# ArbPwrBoost_P2.net
KiCad netlist of a schematic drawn in Altium Designer
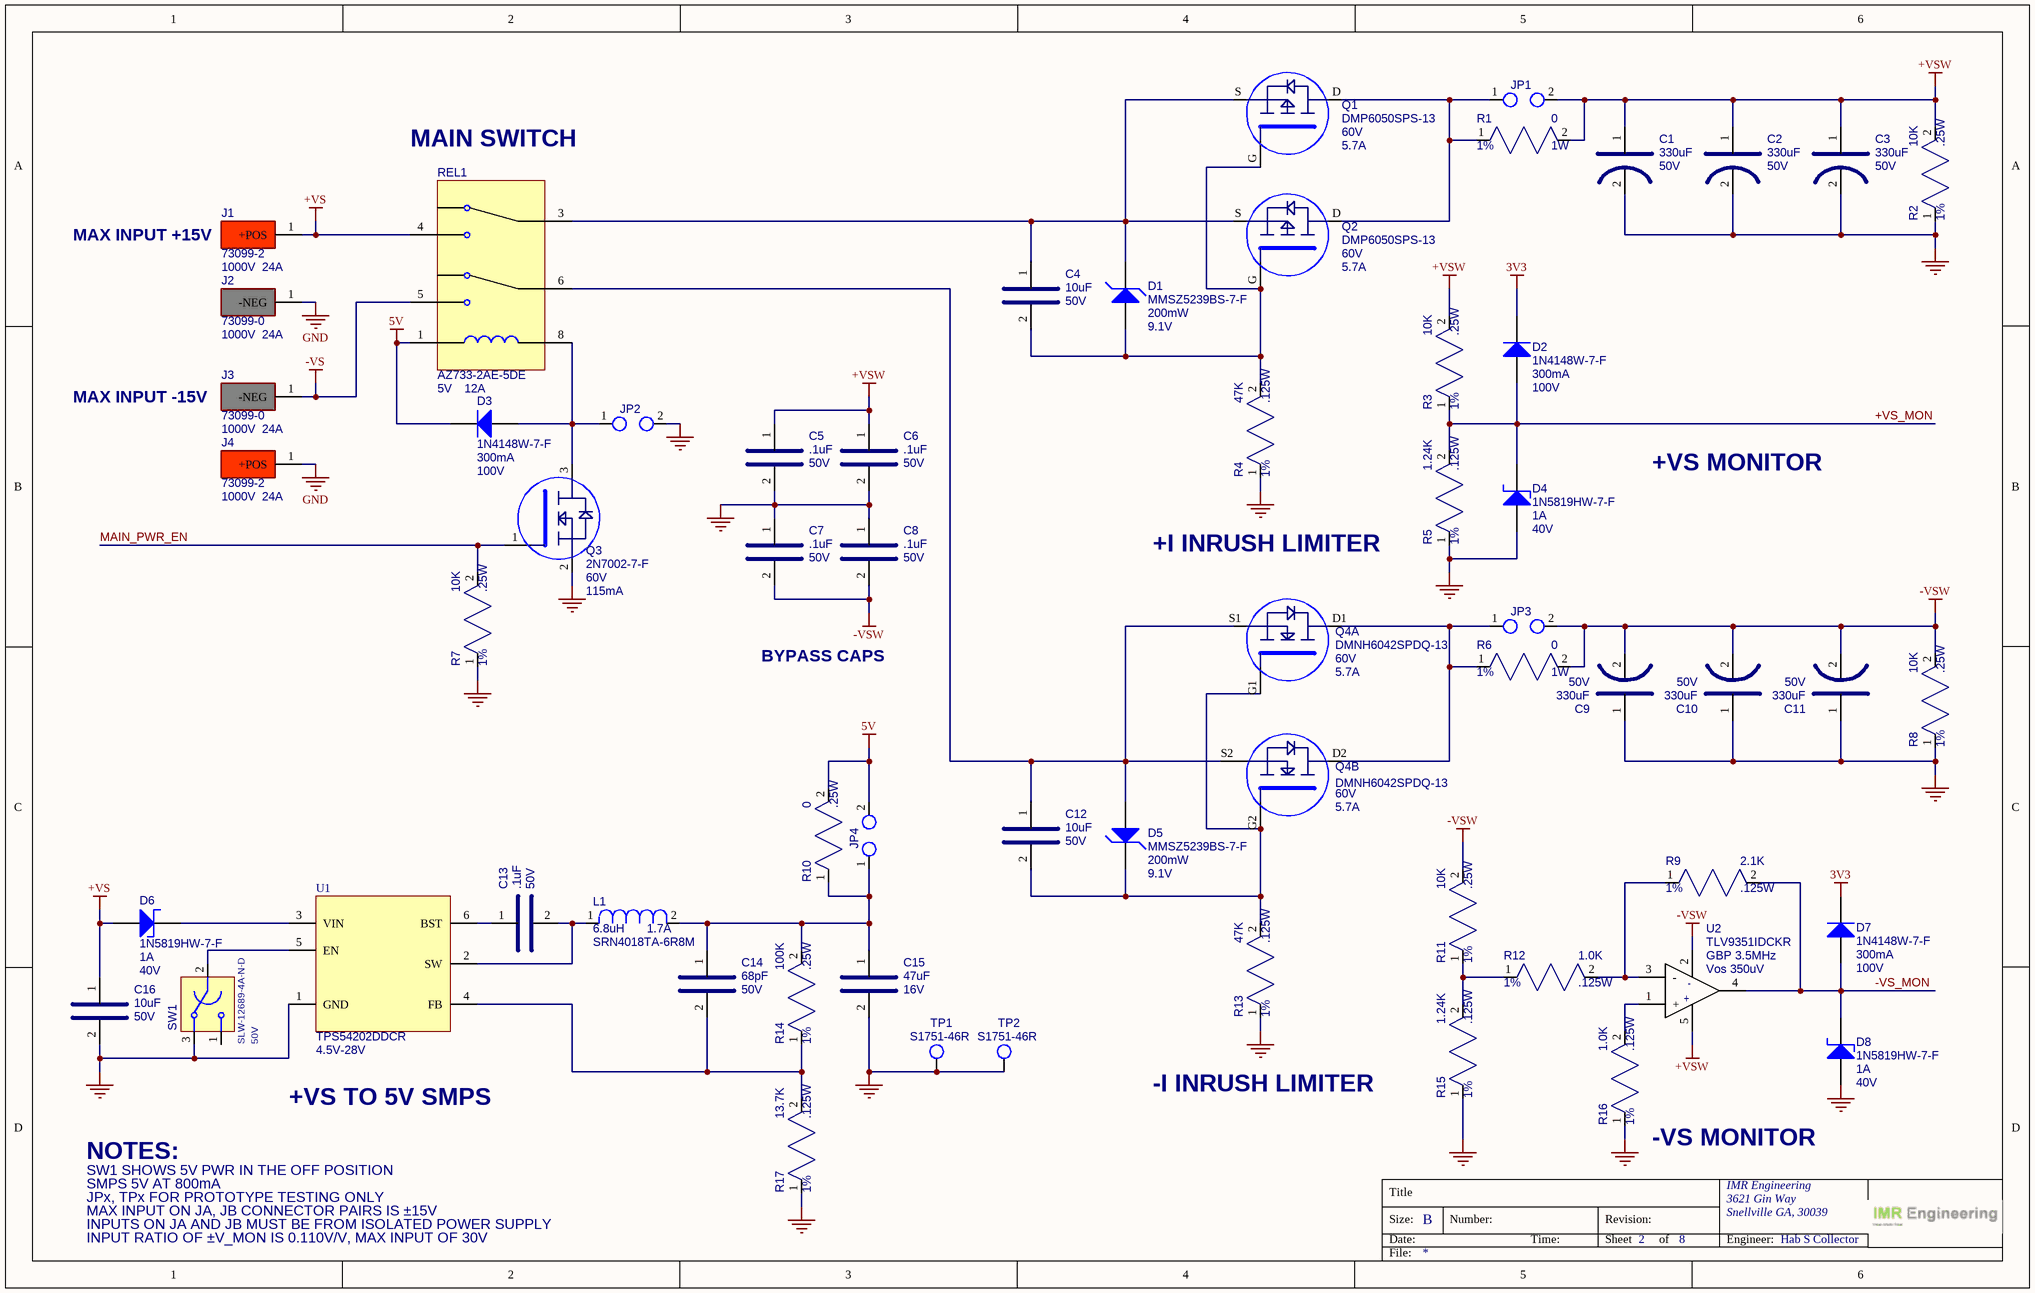
[diagram p0: ArbPwrBoost_P2.SchDoc]

(export (version "E")
  (design (tool "Eeschema 10.0.6"))
  (components
    (comp (ref "C1")
      (value "330uF")
      (footprint "PANASONIC_EEEFK0J332AQ")
      (description "CAP ALE 330UF 20% 50V SMD")
      (fields
        (field (name "MFG") "EEV-FK1H331Q")
        (field (name "VOLTAGE") "50V")
        (field (name "Comment") "Panasonic Electronic")
      )
      (libsource (lib "IMR_LIB_SCH_R2") (part "CAP_330UF_50V_ALE"))
    )
    (comp (ref "C2")
      (value "330uF")
      (footprint "PANASONIC_EEEFK0J332AQ")
      (description "CAP ALE 330UF 20% 50V SMD")
      (fields
        (field (name "MFG") "EEV-FK1H331Q")
        (field (name "VOLTAGE") "50V")
        (field (name "Comment") "Panasonic Electronic")
      )
      (libsource (lib "IMR_LIB_SCH_R2") (part "CAP_330UF_50V_ALE"))
    )
    (comp (ref "C3")
      (value "330uF")
      (footprint "PANASONIC_EEEFK0J332AQ")
      (description "CAP ALE 330UF 20% 50V SMD")
      (fields
        (field (name "MFG") "EEV-FK1H331Q")
        (field (name "VOLTAGE") "50V")
        (field (name "Comment") "Panasonic Electronic")
      )
      (libsource (lib "IMR_LIB_SCH_R2") (part "CAP_330UF_50V_ALE"))
    )
    (comp (ref "C4")
      (value "10uF")
      (footprint "CAP_0805")
      (description "CAP CER 10UF 50V X5R 0805")
      (fields
        (field (name "MFG") "Murata Electronics")
        (field (name "VOLTAGE") "50V")
        (field (name "Comment") "GRM21BR61H106KE43L")
      )
      (libsource (lib "IMR_LIB_SCH_R2") (part "CAP_SMD_10UF_50V_0805"))
    )
    (comp (ref "C5")
      (value ".1uF")
      (footprint "CAP_0805")
      (description "CAP CER 0.1UF 50V X7R 0805")
      (fields
        (field (name "MFG") "KYOCERA AVX")
        (field (name "VOLTAGE") "50V")
        (field (name "Comment") "KGM21NR71H104KT")
      )
      (libsource (lib "IMR_LIB_SCH_R2") (part "CAP_SMD_0.1UF_50V_0805"))
    )
    (comp (ref "C6")
      (value ".1uF")
      (footprint "CAP_0805")
      (description "CAP CER 0.1UF 50V X7R 0805")
      (fields
        (field (name "MFG") "KYOCERA AVX")
        (field (name "VOLTAGE") "50V")
        (field (name "Comment") "KGM21NR71H104KT")
      )
      (libsource (lib "IMR_LIB_SCH_R2") (part "CAP_SMD_0.1UF_50V_0805"))
    )
    (comp (ref "C7")
      (value ".1uF")
      (footprint "CAP_0805")
      (description "CAP CER 0.1UF 50V X7R 0805")
      (fields
        (field (name "MFG") "KYOCERA AVX")
        (field (name "VOLTAGE") "50V")
        (field (name "Comment") "KGM21NR71H104KT")
      )
      (libsource (lib "IMR_LIB_SCH_R2") (part "CAP_SMD_0.1UF_50V_0805"))
    )
    (comp (ref "C8")
      (value ".1uF")
      (footprint "CAP_0805")
      (description "CAP CER 0.1UF 50V X7R 0805")
      (fields
        (field (name "MFG") "KYOCERA AVX")
        (field (name "VOLTAGE") "50V")
        (field (name "Comment") "KGM21NR71H104KT")
      )
      (libsource (lib "IMR_LIB_SCH_R2") (part "CAP_SMD_0.1UF_50V_0805"))
    )
    (comp (ref "C9")
      (value "330uF")
      (footprint "PANASONIC_EEEFK0J332AQ")
      (description "CAP ALE 330UF 20% 50V SMD")
      (fields
        (field (name "MFG") "EEV-FK1H331Q")
        (field (name "VOLTAGE") "50V")
        (field (name "Comment") "Panasonic Electronic")
      )
      (libsource (lib "IMR_LIB_SCH_R2") (part "CAP_330UF_50V_ALE"))
    )
    (comp (ref "C10")
      (value "330uF")
      (footprint "PANASONIC_EEEFK0J332AQ")
      (description "CAP ALE 330UF 20% 50V SMD")
      (fields
        (field (name "MFG") "EEV-FK1H331Q")
        (field (name "VOLTAGE") "50V")
        (field (name "Comment") "Panasonic Electronic")
      )
      (libsource (lib "IMR_LIB_SCH_R2") (part "CAP_330UF_50V_ALE"))
    )
    (comp (ref "C11")
      (value "330uF")
      (footprint "PANASONIC_EEEFK0J332AQ")
      (description "CAP ALE 330UF 20% 50V SMD")
      (fields
        (field (name "MFG") "EEV-FK1H331Q")
        (field (name "VOLTAGE") "50V")
        (field (name "Comment") "Panasonic Electronic")
      )
      (libsource (lib "IMR_LIB_SCH_R2") (part "CAP_330UF_50V_ALE"))
    )
    (comp (ref "C12")
      (value "10uF")
      (footprint "CAP_0805")
      (description "CAP CER 10UF 50V X5R 0805")
      (fields
        (field (name "MFG") "Murata Electronics")
        (field (name "VOLTAGE") "50V")
        (field (name "Comment") "GRM21BR61H106KE43L")
      )
      (libsource (lib "IMR_LIB_SCH_R2") (part "CAP_SMD_10UF_50V_0805"))
    )
    (comp (ref "C13")
      (value ".1uF")
      (footprint "CAP_0805")
      (description "CAP CER 0.1UF 50V X7R 0805")
      (fields
        (field (name "MFG") "KYOCERA AVX")
        (field (name "VOLTAGE") "50V")
        (field (name "Comment") "KGM21NR71H104KT")
      )
      (libsource (lib "IMR_LIB_SCH_R2") (part "CAP_SMD_0.1UF_50V_0805"))
    )
    (comp (ref "C14")
      (value "68pF")
      (footprint "CAP_0805")
      (description "CAP CER 68PF 50V X7R 0805")
      (fields
        (field (name "MFG") "KEMET")
        (field (name "VOLTAGE") "50V")
        (field (name "Comment") "C0805C680K5RACAUTO")
      )
      (libsource (lib "IMR_LIB_SCH_R2") (part "CAP_SMD_68PF_50V_0805"))
    )
    (comp (ref "C15")
      (value "47uF")
      (footprint "CAP_1210")
      (description "CAP CER 47UF 50V X5R 1210")
      (fields
        (field (name "MFG") "Murata Electronics")
        (field (name "VOLTAGE") "16V")
        (field (name "Comment") "GRM32ER60J476ME20L")
      )
      (libsource (lib "IMR_LIB_SCH_R2") (part "CAP_SMD_47UF_16V_1210"))
    )
    (comp (ref "C16")
      (value "10uF")
      (footprint "CAP_0805")
      (description "CAP CER 10UF 50V X5R 0805")
      (fields
        (field (name "MFG") "Murata Electronics")
        (field (name "VOLTAGE") "50V")
        (field (name "Comment") "GRM21BR61H106KE43L")
      )
      (libsource (lib "IMR_LIB_SCH_R2") (part "CAP_SMD_10UF_50V_0805"))
    )
    (comp (ref "D1")
      (value "9.1V")
      (footprint "SOD323")
      (description "DIODE ZENER 9.1V 200MW SOD323")
      (fields
        (field (name "MFG") "Diodes Inc")
        (field (name "MFG_PN") "MMSZ5239BS-7-F")
        (field (name "POWER") "200mW")
        (field (name "Comment") "MMSZ5239BS-7-F")
      )
      (libsource (lib "IMR_LIB_SCH_R2") (part "DIODE_ZENER_MMSZ5239BS-7-F"))
    )
    (comp (ref "D2")
      (value "100V")
      (footprint "SOD123")
      (description "RELAY REED SPDT 250MA 5V")
      (fields
        (field (name "MFG") "Diodes Inc")
        (field (name "MFG_PN") "1N4148W-7-F")
        (field (name "CURRENT") "300mA")
        (field (name "Comment") "1N4148W-7-F")
      )
      (libsource (lib "IMR_LIB_SCH_R2") (part "DIODE_1N4148W-7-F"))
    )
    (comp (ref "D3")
      (value "100V")
      (footprint "SOD123")
      (description "RELAY REED SPDT 250MA 5V")
      (fields
        (field (name "MFG") "Diodes Inc")
        (field (name "MFG_PN") "1N4148W-7-F")
        (field (name "CURRENT") "300mA")
        (field (name "Comment") "1N4148W-7-F")
      )
      (libsource (lib "IMR_LIB_SCH_R2") (part "DIODE_1N4148W-7-F"))
    )
    (comp (ref "D4")
      (value "40V")
      (footprint "SOD123")
      (description "DIODE SCHOTTKY 40V 1A SOD123")
      (fields
        (field (name "MFG") "Diodes Inc")
        (field (name "MFG_PN") "1N5819HW-7-F")
        (field (name "CURRENT") "1A")
        (field (name "Comment") "1N5819HW-7-F")
      )
      (libsource (lib "IMR_LIB_SCH_R2") (part "DIODE_SCHOTTKY_1N5819HW-7-F"))
    )
    (comp (ref "D5")
      (value "9.1V")
      (footprint "SOD323")
      (description "DIODE ZENER 9.1V 200MW SOD323")
      (fields
        (field (name "MFG") "Diodes Inc")
        (field (name "MFG_PN") "MMSZ5239BS-7-F")
        (field (name "POWER") "200mW")
        (field (name "Comment") "MMSZ5239BS-7-F")
      )
      (libsource (lib "IMR_LIB_SCH_R2") (part "DIODE_ZENER_MMSZ5239BS-7-F"))
    )
    (comp (ref "D6")
      (value "40V")
      (footprint "SOD123")
      (description "DIODE SCHOTTKY 40V 1A SOD123")
      (fields
        (field (name "MFG") "Diodes Inc")
        (field (name "MFG_PN") "1N5819HW-7-F")
        (field (name "CURRENT") "1A")
        (field (name "Comment") "1N5819HW-7-F")
      )
      (libsource (lib "IMR_LIB_SCH_R2") (part "DIODE_SCHOTTKY_1N5819HW-7-F"))
    )
    (comp (ref "D7")
      (value "100V")
      (footprint "SOD123")
      (description "RELAY REED SPDT 250MA 5V")
      (fields
        (field (name "MFG") "Diodes Inc")
        (field (name "MFG_PN") "1N4148W-7-F")
        (field (name "CURRENT") "300mA")
        (field (name "Comment") "1N4148W-7-F")
      )
      (libsource (lib "IMR_LIB_SCH_R2") (part "DIODE_1N4148W-7-F"))
    )
    (comp (ref "D8")
      (value "40V")
      (footprint "SOD123")
      (description "DIODE SCHOTTKY 40V 1A SOD123")
      (fields
        (field (name "MFG") "Diodes Inc")
        (field (name "MFG_PN") "1N5819HW-7-F")
        (field (name "CURRENT") "1A")
        (field (name "Comment") "1N5819HW-7-F")
      )
      (libsource (lib "IMR_LIB_SCH_R2") (part "DIODE_SCHOTTKY_1N5819HW-7-F"))
    )
    (comp (ref "J1")
      (value "1000V")
      (footprint "Pomona_73099-2")
      (description "CONN 4mm Banana Socket Right Angle PCB RED")
      (fields
        (field (name "MFG") "Pomona")
        (field (name "MFG_PN") "73099-2")
        (field (name "CURRENT") "24A")
        (field (name "Comment") "73099-2")
      )
      (libsource (lib "IMR_LIB_SCH_R2") (part "CONN_PANOMA_73099-2"))
    )
    (comp (ref "J2")
      (value "1000V")
      (footprint "Pomona_73099-0")
      (description "CONN 4mm Banana Socket Right Angle PCB BLK")
      (fields
        (field (name "MFG") "Pomona")
        (field (name "MFG_PN") "73099-0")
        (field (name "CURRENT") "24A")
        (field (name "Comment") "73099-0")
      )
      (libsource (lib "IMR_LIB_SCH_R2") (part "CONN_PANOMA_73099-0"))
    )
    (comp (ref "J3")
      (value "1000V")
      (footprint "Pomona_73099-0")
      (description "CONN 4mm Banana Socket Right Angle PCB BLK")
      (fields
        (field (name "MFG") "Pomona")
        (field (name "MFG_PN") "73099-0")
        (field (name "CURRENT") "24A")
        (field (name "Comment") "73099-0")
      )
      (libsource (lib "IMR_LIB_SCH_R2") (part "CONN_PANOMA_73099-0"))
    )
    (comp (ref "J4")
      (value "1000V")
      (footprint "Pomona_73099-2")
      (description "CONN 4mm Banana Socket Right Angle PCB RED")
      (fields
        (field (name "MFG") "Pomona")
        (field (name "MFG_PN") "73099-2")
        (field (name "CURRENT") "24A")
        (field (name "Comment") "73099-2")
      )
      (libsource (lib "IMR_LIB_SCH_R2") (part "CONN_PANOMA_73099-2"))
    )
    (comp (ref "JP1")
      (value "PREC002SFAN-RC")
      (footprint "HDR_1X2_100MILL")
      (description "CONN HEADER VERT 2POS 2.54MM")
      (fields (field (name "MFG") "Sullins Connector Solutions"))
      (libsource (lib "IMR_LIB_SCH_R2") (part "CONN_JUMPER_2P_100MIL_VERT"))
    )
    (comp (ref "JP2")
      (value "PREC002SFAN-RC")
      (footprint "HDR_1X2_100MILL")
      (description "CONN HEADER VERT 2POS 2.54MM")
      (fields (field (name "MFG") "Sullins Connector Solutions"))
      (libsource (lib "IMR_LIB_SCH_R2") (part "CONN_JUMPER_2P_100MIL_VERT"))
    )
    (comp (ref "JP3")
      (value "PREC002SFAN-RC")
      (footprint "HDR_1X2_100MILL")
      (description "CONN HEADER VERT 2POS 2.54MM")
      (fields (field (name "MFG") "Sullins Connector Solutions"))
      (libsource (lib "IMR_LIB_SCH_R2") (part "CONN_JUMPER_2P_100MIL_VERT"))
    )
    (comp (ref "JP4")
      (value "PREC002SFAN-RC")
      (footprint "HDR_1X2_100MILL")
      (description "CONN HEADER VERT 2POS 2.54MM")
      (fields (field (name "MFG") "Sullins Connector Solutions"))
      (libsource (lib "IMR_LIB_SCH_R2") (part "CONN_JUMPER_2P_100MIL_VERT"))
    )
    (comp (ref "L1")
      (value "6.8uH")
      (footprint "SRN4018TA")
      (description "FIXED IND 6.8UH 1.7A 98 MOHM SMD")
      (fields
        (field (name "MFG") "Bourns Inc.")
        (field (name "TOLERANCE") "20%")
        (field (name "MFG_PN") "SRN4018TA-6R8M")
        (field (name "CURRENT") "1.7A")
      )
      (libsource (lib "IMR_LIB_SCH_R2") (part "INDUCTOR_SRN4018TA-6R8M"))
    )
    (comp (ref "Q1")
      (value "60V")
      (footprint "DMP3007SPS13")
      (description "MOSFET P-CH 60V 5.7A PWRDI5060-8")
      (fields
        (field (name "MFG") "Diodes Inc")
        (field (name "MFG_PN") "DMP6050SPS-13")
        (field (name "CURRENT") "5.7A")
        (field (name "Comment") "DMP6050SPS-13")
      )
      (libsource (lib "IMR_LIB_SCH_R2") (part "MOSFET_PCH_DMP6050SPS-13"))
    )
    (comp (ref "Q2")
      (value "60V")
      (footprint "DMP3007SPS13")
      (description "MOSFET P-CH 60V 5.7A PWRDI5060-8")
      (fields
        (field (name "MFG") "Diodes Inc")
        (field (name "MFG_PN") "DMP6050SPS-13")
        (field (name "CURRENT") "5.7A")
        (field (name "Comment") "DMP6050SPS-13")
      )
      (libsource (lib "IMR_LIB_SCH_R2") (part "MOSFET_PCH_DMP6050SPS-13"))
    )
    (comp (ref "Q3")
      (value "60V")
      (footprint "SOT-23")
      (description "MOSFET N-CH 60V 115MA SOT23-3")
      (fields
        (field (name "MFG") "Diodes Inc")
        (field (name "MFG_PN") "2N7002-7-F")
        (field (name "CURRENT") "115mA")
        (field (name "Comment") "2N7002-7-F")
      )
      (libsource (lib "IMR_LIB_SCH_R2") (part "MOSFET_NCH_2N7002-7-F"))
    )
    (comp (ref "Q4")
      (value "60V")
      (footprint "TRANS_DMP2002UPS-13")
      (description "MOSFET NCH 60V 5.7A POWERDI")
      (fields
        (field (name "MFG") "Diodes Inc")
        (field (name "MFG_PN") "DMNH6042SPDQ-13")
        (field (name "CURRENT") "5.7A")
        (field (name "Comment") "DMNH6042SPDQ-13")
      )
      (libsource (lib "IMR_LIB_SCH_R2") (part "MOSFET_NCH_DMNH6042SPDQ-13"))
    )
    (comp (ref "R1")
      (value "0")
      (footprint "RES_2512")
      (description "RES SMD 0 OHM 1% 1W 2512")
      (fields
        (field (name "MFG") "Yageo")
        (field (name "TOLERANCE") "1%")
        (field (name "POWER") "1W")
        (field (name "Comment") "RC2512JK-070RL")
      )
      (libsource (lib "IMR_LIB_SCH_R2") (part "RES_SMD_0_2512_1W_1%"))
    )
    (comp (ref "R2")
      (value "10K")
      (footprint "RES_0805")
      (description "RES SMD 10K OHM 1% 1/4W 0805")
      (fields
        (field (name "MFG") "Yageo")
        (field (name "POWER") ".25W")
        (field (name "TOLERANCE") "1%")
        (field (name "Comment") "RC0805FR-7W10KL")
      )
      (libsource (lib "IMR_LIB_SCH_R2") (part "RES_SMD_10K_0805_1/4W_1%"))
    )
    (comp (ref "R3")
      (value "10K")
      (footprint "RES_0805")
      (description "RES SMD 10K OHM 1% 1/4W 0805")
      (fields
        (field (name "MFG") "Yageo")
        (field (name "POWER") ".25W")
        (field (name "TOLERANCE") "1%")
        (field (name "Comment") "RC0805FR-7W10KL")
      )
      (libsource (lib "IMR_LIB_SCH_R2") (part "RES_SMD_10K_0805_1/4W_1%"))
    )
    (comp (ref "R4")
      (value "47K")
      (footprint "RES_0805")
      (description "RES SMD 47K OHM 1% 1/8W 0805")
      (fields
        (field (name "MFG") "Yageo")
        (field (name "POWER") ".125W")
        (field (name "TOLERANCE") "1%")
        (field (name "Comment") "RC0805FR-1347KL")
      )
      (libsource (lib "IMR_LIB_SCH_R2") (part "RES_SMD_47K_0805_1/8W_1%"))
    )
    (comp (ref "R5")
      (value "1.24K")
      (footprint "RES_0805")
      (description "RES SMD 1.24K OHM 1% 1/8W 0805")
      (fields
        (field (name "MFG") "Yageo")
        (field (name "POWER") ".125W")
        (field (name "TOLERANCE") "1%")
        (field (name "Comment") "RC0805FR-071K24L")
      )
      (libsource (lib "IMR_LIB_SCH_R2") (part "RES_SMD_1.24K_0805_1/8W_1%"))
    )
    (comp (ref "R6")
      (value "0")
      (footprint "RES_2512")
      (description "RES SMD 0 OHM 1% 1W 2512")
      (fields
        (field (name "MFG") "Yageo")
        (field (name "TOLERANCE") "1%")
        (field (name "POWER") "1W")
        (field (name "Comment") "RC2512JK-070RL")
      )
      (libsource (lib "IMR_LIB_SCH_R2") (part "RES_SMD_0_2512_1W_1%"))
    )
    (comp (ref "R7")
      (value "10K")
      (footprint "RES_0805")
      (description "RES SMD 10K OHM 1% 1/4W 0805")
      (fields
        (field (name "MFG") "Yageo")
        (field (name "POWER") ".25W")
        (field (name "TOLERANCE") "1%")
        (field (name "Comment") "RC0805FR-7W10KL")
      )
      (libsource (lib "IMR_LIB_SCH_R2") (part "RES_SMD_10K_0805_1/4W_1%"))
    )
    (comp (ref "R8")
      (value "10K")
      (footprint "RES_0805")
      (description "RES SMD 10K OHM 1% 1/4W 0805")
      (fields
        (field (name "MFG") "Yageo")
        (field (name "POWER") ".25W")
        (field (name "TOLERANCE") "1%")
        (field (name "Comment") "RC0805FR-7W10KL")
      )
      (libsource (lib "IMR_LIB_SCH_R2") (part "RES_SMD_10K_0805_1/4W_1%"))
    )
    (comp (ref "R9")
      (value "2.1K")
      (footprint "RES_0805")
      (description "RES SMD 2.1K OHM 1% 1/8W 0805")
      (fields
        (field (name "MFG") "Yageo")
        (field (name "POWER") ".125W")
        (field (name "TOLERANCE") "1%")
        (field (name "Comment") "RC0805FR-072K1L")
      )
      (libsource (lib "IMR_LIB_SCH_R2") (part "RES_SMD_2.1K_0805_1/8W_1%"))
    )
    (comp (ref "R10")
      (value "0")
      (footprint "RES_0805")
      (description "RES SMD 0 OHM 1% 1/8W 0805")
      (fields (field (name "MFG") "Yageo") (field (name "TOLERANCE") "1%") (field (name "POWER") ".25W"))
      (libsource (lib "IMR_LIB_SCH_R2") (part "RES_SMD_0_0805_1/8W_1%"))
    )
    (comp (ref "R11")
      (value "10K")
      (footprint "RES_0805")
      (description "RES SMD 10K OHM 1% 1/4W 0805")
      (fields
        (field (name "MFG") "Yageo")
        (field (name "POWER") ".25W")
        (field (name "TOLERANCE") "1%")
        (field (name "Comment") "RC0805FR-7W10KL")
      )
      (libsource (lib "IMR_LIB_SCH_R2") (part "RES_SMD_10K_0805_1/4W_1%"))
    )
    (comp (ref "R12")
      (value "1.0K")
      (footprint "RES_0805")
      (description "RES SMD 1.0K OHM 1% 1/8W 0805")
      (fields
        (field (name "MFG") "Yageo")
        (field (name "POWER") ".125W")
        (field (name "TOLERANCE") "1%")
        (field (name "Comment") "RC0805FR-071KL")
      )
      (libsource (lib "IMR_LIB_SCH_R2") (part "RES_SMD_1.0K_0805_1/8W_1%"))
    )
    (comp (ref "R13")
      (value "47K")
      (footprint "RES_0805")
      (description "RES SMD 47K OHM 1% 1/8W 0805")
      (fields
        (field (name "MFG") "Yageo")
        (field (name "POWER") ".125W")
        (field (name "TOLERANCE") "1%")
        (field (name "Comment") "RC0805FR-1347KL")
      )
      (libsource (lib "IMR_LIB_SCH_R2") (part "RES_SMD_47K_0805_1/8W_1%"))
    )
    (comp (ref "R14")
      (value "100K")
      (footprint "RES_0805")
      (description "RES SMD 100K OHM 1% 1/4W 0805")
      (fields
        (field (name "MFG") "Yageo")
        (field (name "POWER") ".25W")
        (field (name "TOLERANCE") "1%")
        (field (name "Comment") "RC0805FR-07100KL")
      )
      (libsource (lib "IMR_LIB_SCH_R2") (part "RES_SMD_100K_0805_1/4W_1%"))
    )
    (comp (ref "R15")
      (value "1.24K")
      (footprint "RES_0805")
      (description "RES SMD 1.24K OHM 1% 1/8W 0805")
      (fields
        (field (name "MFG") "Yageo")
        (field (name "POWER") ".125W")
        (field (name "TOLERANCE") "1%")
        (field (name "Comment") "RC0805FR-071K24L")
      )
      (libsource (lib "IMR_LIB_SCH_R2") (part "RES_SMD_1.24K_0805_1/8W_1%"))
    )
    (comp (ref "R16")
      (value "1.0K")
      (footprint "RES_0805")
      (description "RES SMD 1.0K OHM 1% 1/8W 0805")
      (fields
        (field (name "MFG") "Yageo")
        (field (name "POWER") ".125W")
        (field (name "TOLERANCE") "1%")
        (field (name "Comment") "RC0805FR-071KL")
      )
      (libsource (lib "IMR_LIB_SCH_R2") (part "RES_SMD_1.0K_0805_1/8W_1%"))
    )
    (comp (ref "R17")
      (value "13.7K")
      (footprint "RES_0805")
      (description "RES SMD 13.7K OHM 1% 1/8W 0805")
      (fields
        (field (name "MFG") "Yageo")
        (field (name "POWER") ".125W")
        (field (name "TOLERANCE") "1%")
        (field (name "Comment") "RC0805FR-0713K7L")
      )
      (libsource (lib "IMR_LIB_SCH_R2") (part "RES_SMD_13.7K_0805_1/8W_1%"))
    )
    (comp (ref "REL1")
      (value "5V")
      (footprint "AZ733")
      (description "RELAY REED SPDT 250MA 5V")
      (fields
        (field (name "MFG") "American Zettler")
        (field (name "MFG_PN") "AZ733-2AE-5DE")
        (field (name "CURRENT") "12A")
        (field (name "Comment") "AZ733-2AE-5DE")
      )
      (libsource (lib "IMR_LIB_SCH_R2") (part "RELAY_AZ733-2AE-5DE"))
    )
    (comp (ref "SW1")
      (value "50V")
      (footprint "SLW126894AND")
      (description "SWITCH SLIDE SPDT 300MA 50V")
      (fields
        (field (name "MFG") "Same Sky")
        (field (name "MFG_PN") "SLW-12689-4A-N-D")
        (field (name "Comment") "SLW-12689-4A-N-D")
      )
      (libsource (lib "IMR_LIB_SCH_R2") (part "SWITCH_SLW-12689-4A-N-D"))
    )
    (comp (ref "TP1")
      (value "S1751-46R")
      (footprint "HARWIN_S1751")
      (description "PCB TEST POINT CONNECT")
      (fields (field (name "MFG") "Harwin Inc") (field (name "MFG_PN") "S1751-46R"))
      (libsource (lib "IMR_LIB_SCH_R2") (part "CONN_TEST_POINT_S1751-46R"))
    )
    (comp (ref "TP2")
      (value "S1751-46R")
      (footprint "HARWIN_S1751")
      (description "PCB TEST POINT CONNECT")
      (fields (field (name "MFG") "Harwin Inc") (field (name "MFG_PN") "S1751-46R"))
      (libsource (lib "IMR_LIB_SCH_R2") (part "CONN_TEST_POINT_S1751-46R"))
    )
    (comp (ref "U1")
      (value "4.5V-28V")
      (footprint "SOT-23-6")
      (description "IC REG BUCK ADJ 2A SOT23")
      (fields
        (field (name "MFG") "Texas Instruments")
        (field (name "MFG_PN") "TPS54202DDCR")
        (field (name "Comment") "TPS54202DDCR")
      )
      (libsource (lib "IMR_LIB_SCH") (part "IC_TPS54202DDCR"))
    )
    (comp (ref "U2")
      (value "GBP 3.5MHz")
      (footprint "SOT-353")
      (description "IC OPAMP GP 3.5MHZ 350uV C70-5")
      (fields
        (field (name "MFG") "Texas Instruments")
        (field (name "MFG_PN") "TLV9351IDCKR")
        (field (name "VOS") "Vos 350uV")
        (field (name "Comment") "TLV9351IDCKR")
      )
      (libsource (lib "IMR_LIB_SCH_R2") (part "OPAMP_TLV9351IDCKR"))
    )
  )
  (nets
    (net (code "1") (name "+VS") (class "Default")
      (node (ref "C16") (pin "1") (pinfunction "1_1") (pintype "passive"))
      (node (ref "D6") (pin "1") (pinfunction "A_1") (pintype "passive"))
      (node (ref "J1") (pin "1") (pinfunction "+POS_1") (pintype "passive"))
      (node (ref "REL1") (pin "4") (pintype "passive"))
    )
    (net (code "2") (name "+VSW") (class "Default")
      (node (ref "C1") (pin "1") (pinfunction "1_1") (pintype "passive"))
      (node (ref "C2") (pin "1") (pinfunction "1_1") (pintype "passive"))
      (node (ref "C3") (pin "1") (pinfunction "1_1") (pintype "passive"))
      (node (ref "C5") (pin "1") (pinfunction "1_1") (pintype "passive"))
      (node (ref "C6") (pin "1") (pinfunction "1_1") (pintype "passive"))
      (node (ref "JP1") (pin "2") (pintype "passive"))
      (node (ref "R1") (pin "2") (pinfunction "2_2") (pintype "passive"))
      (node (ref "R2") (pin "2") (pinfunction "2_2") (pintype "passive"))
      (node (ref "R3") (pin "2") (pinfunction "2_2") (pintype "passive"))
      (node (ref "U2") (pin "5") (pintype "passive"))
    )
    (net (code "3") (name "-VS") (class "Default")
      (node (ref "J3") (pin "1") (pinfunction "-NEG_1") (pintype "passive"))
      (node (ref "REL1") (pin "5") (pintype "passive"))
    )
    (net (code "4") (name "-VSW") (class "Default")
      (node (ref "C10") (pin "2") (pinfunction "2_2") (pintype "passive"))
      (node (ref "C11") (pin "2") (pinfunction "2_2") (pintype "passive"))
      (node (ref "C7") (pin "2") (pinfunction "2_2") (pintype "passive"))
      (node (ref "C8") (pin "2") (pinfunction "2_2") (pintype "passive"))
      (node (ref "C9") (pin "2") (pinfunction "2_2") (pintype "passive"))
      (node (ref "JP3") (pin "2") (pintype "passive"))
      (node (ref "R11") (pin "2") (pinfunction "2_2") (pintype "passive"))
      (node (ref "R6") (pin "2") (pinfunction "2_2") (pintype "passive"))
      (node (ref "R8") (pin "2") (pinfunction "2_2") (pintype "passive"))
      (node (ref "U2") (pin "2") (pintype "passive"))
    )
    (net (code "5") (name "/+VS_MON") (class "Default")
      (node (ref "D2") (pin "1") (pinfunction "A_1") (pintype "passive"))
      (node (ref "D4") (pin "2") (pinfunction "K_2") (pintype "passive"))
      (node (ref "R3") (pin "1") (pinfunction "1_1") (pintype "passive"))
      (node (ref "R5") (pin "2") (pinfunction "2_2") (pintype "passive"))
    )
    (net (code "6") (name "/-VS_MON") (class "Default")
      (node (ref "D7") (pin "1") (pinfunction "A_1") (pintype "passive"))
      (node (ref "D8") (pin "2") (pinfunction "K_2") (pintype "passive"))
      (node (ref "R9") (pin "2") (pinfunction "2_2") (pintype "passive"))
      (node (ref "U2") (pin "4") (pintype "passive"))
    )
    (net (code "7") (name "/MAIN_PWR_EN") (class "Default")
      (node (ref "Q3") (pin "1") (pinfunction "B_1") (pintype "passive"))
      (node (ref "R7") (pin "2") (pinfunction "2_2") (pintype "passive"))
    )
    (net (code "8") (name "3V3") (class "Default")
      (node (ref "D2") (pin "2") (pinfunction "K_2") (pintype "passive"))
      (node (ref "D7") (pin "2") (pinfunction "K_2") (pintype "passive"))
    )
    (net (code "9") (name "5V") (class "Default")
      (node (ref "D3") (pin "2") (pinfunction "K_2") (pintype "passive"))
      (node (ref "JP4") (pin "2") (pintype "passive"))
      (node (ref "R10") (pin "2") (pinfunction "2_2") (pintype "passive"))
      (node (ref "REL1") (pin "1") (pintype "passive"))
    )
    (net (code "10") (name "GND") (class "Default")
      (node (ref "C1") (pin "2") (pinfunction "2_2") (pintype "passive"))
      (node (ref "C10") (pin "1") (pinfunction "1_1") (pintype "passive"))
      (node (ref "C11") (pin "1") (pinfunction "1_1") (pintype "passive"))
      (node (ref "C15") (pin "2") (pinfunction "2_2") (pintype "passive"))
      (node (ref "C16") (pin "2") (pinfunction "2_2") (pintype "passive"))
      (node (ref "C2") (pin "2") (pinfunction "2_2") (pintype "passive"))
      (node (ref "C3") (pin "2") (pinfunction "2_2") (pintype "passive"))
      (node (ref "C5") (pin "2") (pinfunction "2_2") (pintype "passive"))
      (node (ref "C6") (pin "2") (pinfunction "2_2") (pintype "passive"))
      (node (ref "C7") (pin "1") (pinfunction "1_1") (pintype "passive"))
      (node (ref "C8") (pin "1") (pinfunction "1_1") (pintype "passive"))
      (node (ref "C9") (pin "1") (pinfunction "1_1") (pintype "passive"))
      (node (ref "D4") (pin "1") (pinfunction "A_1") (pintype "passive"))
      (node (ref "D8") (pin "1") (pinfunction "A_1") (pintype "passive"))
      (node (ref "J2") (pin "1") (pinfunction "-NEG_1") (pintype "passive"))
      (node (ref "J4") (pin "1") (pinfunction "+POS_1") (pintype "passive"))
      (node (ref "JP2") (pin "2") (pintype "passive"))
      (node (ref "Q3") (pin "2") (pinfunction "E_2") (pintype "passive"))
      (node (ref "R13") (pin "1") (pinfunction "1_1") (pintype "passive"))
      (node (ref "R15") (pin "1") (pinfunction "1_1") (pintype "passive"))
      (node (ref "R16") (pin "1") (pinfunction "1_1") (pintype "passive"))
      (node (ref "R17") (pin "1") (pinfunction "1_1") (pintype "passive"))
      (node (ref "R2") (pin "1") (pinfunction "1_1") (pintype "passive"))
      (node (ref "R4") (pin "1") (pinfunction "1_1") (pintype "passive"))
      (node (ref "R5") (pin "1") (pinfunction "1_1") (pintype "passive"))
      (node (ref "R7") (pin "1") (pinfunction "1_1") (pintype "passive"))
      (node (ref "R8") (pin "1") (pinfunction "1_1") (pintype "passive"))
      (node (ref "SW1") (pin "3") (pintype "passive"))
      (node (ref "TP1") (pin "1") (pintype "passive"))
      (node (ref "TP2") (pin "1") (pintype "passive"))
      (node (ref "U1") (pin "1") (pinfunction "GND_1") (pintype "passive"))
    )
    (net (code "11") (name "Net-(C14-Pad1)") (class "Default")
      (node (ref "C14") (pin "1") (pinfunction "1_1") (pintype "passive"))
      (node (ref "C15") (pin "1") (pinfunction "1_1") (pintype "passive"))
      (node (ref "JP4") (pin "1") (pintype "passive"))
      (node (ref "L1") (pin "2") (pinfunction "2_2") (pintype "passive"))
      (node (ref "R10") (pin "1") (pinfunction "1_1") (pintype "passive"))
      (node (ref "R14") (pin "2") (pinfunction "2_2") (pintype "passive"))
    )
    (net (code "12") (name "Net-(D1-A)") (class "Default")
      (node (ref "C4") (pin "2") (pinfunction "2_2") (pintype "passive"))
      (node (ref "D1") (pin "1") (pinfunction "A_1") (pintype "passive"))
      (node (ref "Q1") (pin "G") (pinfunction "G_G") (pintype "passive"))
      (node (ref "Q2") (pin "G") (pinfunction "G_G") (pintype "passive"))
      (node (ref "R4") (pin "2") (pinfunction "2_2") (pintype "passive"))
    )
    (net (code "13") (name "Net-(D1-K)") (class "Default")
      (node (ref "C4") (pin "1") (pinfunction "1_1") (pintype "passive"))
      (node (ref "D1") (pin "2") (pinfunction "K_2") (pintype "passive"))
      (node (ref "Q1") (pin "S") (pinfunction "S_S") (pintype "passive"))
      (node (ref "Q2") (pin "S") (pinfunction "S_S") (pintype "passive"))
      (node (ref "REL1") (pin "3") (pintype "passive"))
    )
    (net (code "14") (name "Net-(D3-A)") (class "Default")
      (node (ref "D3") (pin "1") (pinfunction "A_1") (pintype "passive"))
      (node (ref "JP2") (pin "1") (pintype "passive"))
      (node (ref "Q3") (pin "3") (pinfunction "C_3") (pintype "passive"))
      (node (ref "REL1") (pin "8") (pintype "passive"))
    )
    (net (code "15") (name "Net-(D5-A)") (class "Default")
      (node (ref "C12") (pin "1") (pinfunction "1_1") (pintype "passive"))
      (node (ref "D5") (pin "1") (pinfunction "A_1") (pintype "passive"))
      (node (ref "Q4") (pin "S1") (pinfunction "S_S1") (pintype "passive"))
      (node (ref "Q4") (pin "S2") (pinfunction "S_S2") (pintype "passive"))
      (node (ref "REL1") (pin "6") (pintype "passive"))
    )
    (net (code "16") (name "Net-(D5-K)") (class "Default")
      (node (ref "C12") (pin "2") (pinfunction "2_2") (pintype "passive"))
      (node (ref "D5") (pin "2") (pinfunction "K_2") (pintype "passive"))
      (node (ref "Q4") (pin "G1") (pinfunction "G_G1") (pintype "passive"))
      (node (ref "Q4") (pin "G2") (pintype "passive"))
      (node (ref "R13") (pin "2") (pinfunction "2_2") (pintype "passive"))
    )
    (net (code "17") (name "Net-(D6-K)") (class "Default")
      (node (ref "D6") (pin "2") (pinfunction "K_2") (pintype "passive"))
      (node (ref "U1") (pin "3") (pinfunction "VIN_3") (pintype "passive"))
    )
    (net (code "18") (name "Net-(JP1-Pad1)") (class "Default")
      (node (ref "JP1") (pin "1") (pintype "passive"))
      (node (ref "Q1") (pin "D") (pinfunction "D_D") (pintype "passive"))
      (node (ref "Q2") (pin "D") (pinfunction "D_D") (pintype "passive"))
      (node (ref "R1") (pin "1") (pinfunction "1_1") (pintype "passive"))
    )
    (net (code "19") (name "Net-(Q4A-D)") (class "Default")
      (node (ref "JP3") (pin "1") (pintype "passive"))
      (node (ref "Q4") (pin "D1") (pinfunction "D_D1") (pintype "passive"))
      (node (ref "Q4") (pin "D2") (pinfunction "D_D2") (pintype "passive"))
      (node (ref "R6") (pin "1") (pinfunction "1_1") (pintype "passive"))
    )
    (net (code "20") (name "Net-(R11-Pad1)") (class "Default")
      (node (ref "R11") (pin "1") (pinfunction "1_1") (pintype "passive"))
      (node (ref "R12") (pin "1") (pinfunction "1_1") (pintype "passive"))
      (node (ref "R15") (pin "2") (pinfunction "2_2") (pintype "passive"))
    )
    (net (code "21") (name "Net-(U1-BST)") (class "Default")
      (node (ref "C13") (pin "1") (pinfunction "1_1") (pintype "passive"))
      (node (ref "U1") (pin "6") (pinfunction "BST_6") (pintype "passive"))
    )
    (net (code "22") (name "Net-(U1-EN)") (class "Default")
      (node (ref "SW1") (pin "2") (pintype "passive"))
      (node (ref "U1") (pin "5") (pinfunction "EN_5") (pintype "passive"))
    )
    (net (code "23") (name "Net-(U1-FB)") (class "Default")
      (node (ref "C14") (pin "2") (pinfunction "2_2") (pintype "passive"))
      (node (ref "R14") (pin "1") (pinfunction "1_1") (pintype "passive"))
      (node (ref "R17") (pin "2") (pinfunction "2_2") (pintype "passive"))
      (node (ref "U1") (pin "4") (pinfunction "FB_4") (pintype "passive"))
    )
    (net (code "24") (name "Net-(U1-SW)") (class "Default")
      (node (ref "C13") (pin "2") (pinfunction "2_2") (pintype "passive"))
      (node (ref "L1") (pin "1") (pinfunction "1_1") (pintype "passive"))
      (node (ref "U1") (pin "2") (pinfunction "SW_2") (pintype "passive"))
    )
    (net (code "25") (name "Net-(U2-+)") (class "Default")
      (node (ref "R16") (pin "2") (pinfunction "2_2") (pintype "passive"))
      (node (ref "U2") (pin "1") (pinfunction "+_1") (pintype "passive"))
    )
    (net (code "26") (name "Net-(U2--)") (class "Default")
      (node (ref "R12") (pin "2") (pinfunction "2_2") (pintype "passive"))
      (node (ref "R9") (pin "1") (pinfunction "1_1") (pintype "passive"))
      (node (ref "U2") (pin "3") (pinfunction "-_3") (pintype "passive"))
    )
    (net (code "27") (name "unconnected-(SW1-Pad1)") (class "Default")
      (node (ref "SW1") (pin "1") (pintype "passive"))
    )
  )
)
